# ch552t.net
KiCad netlist of a schematic drawn in Altium Designer
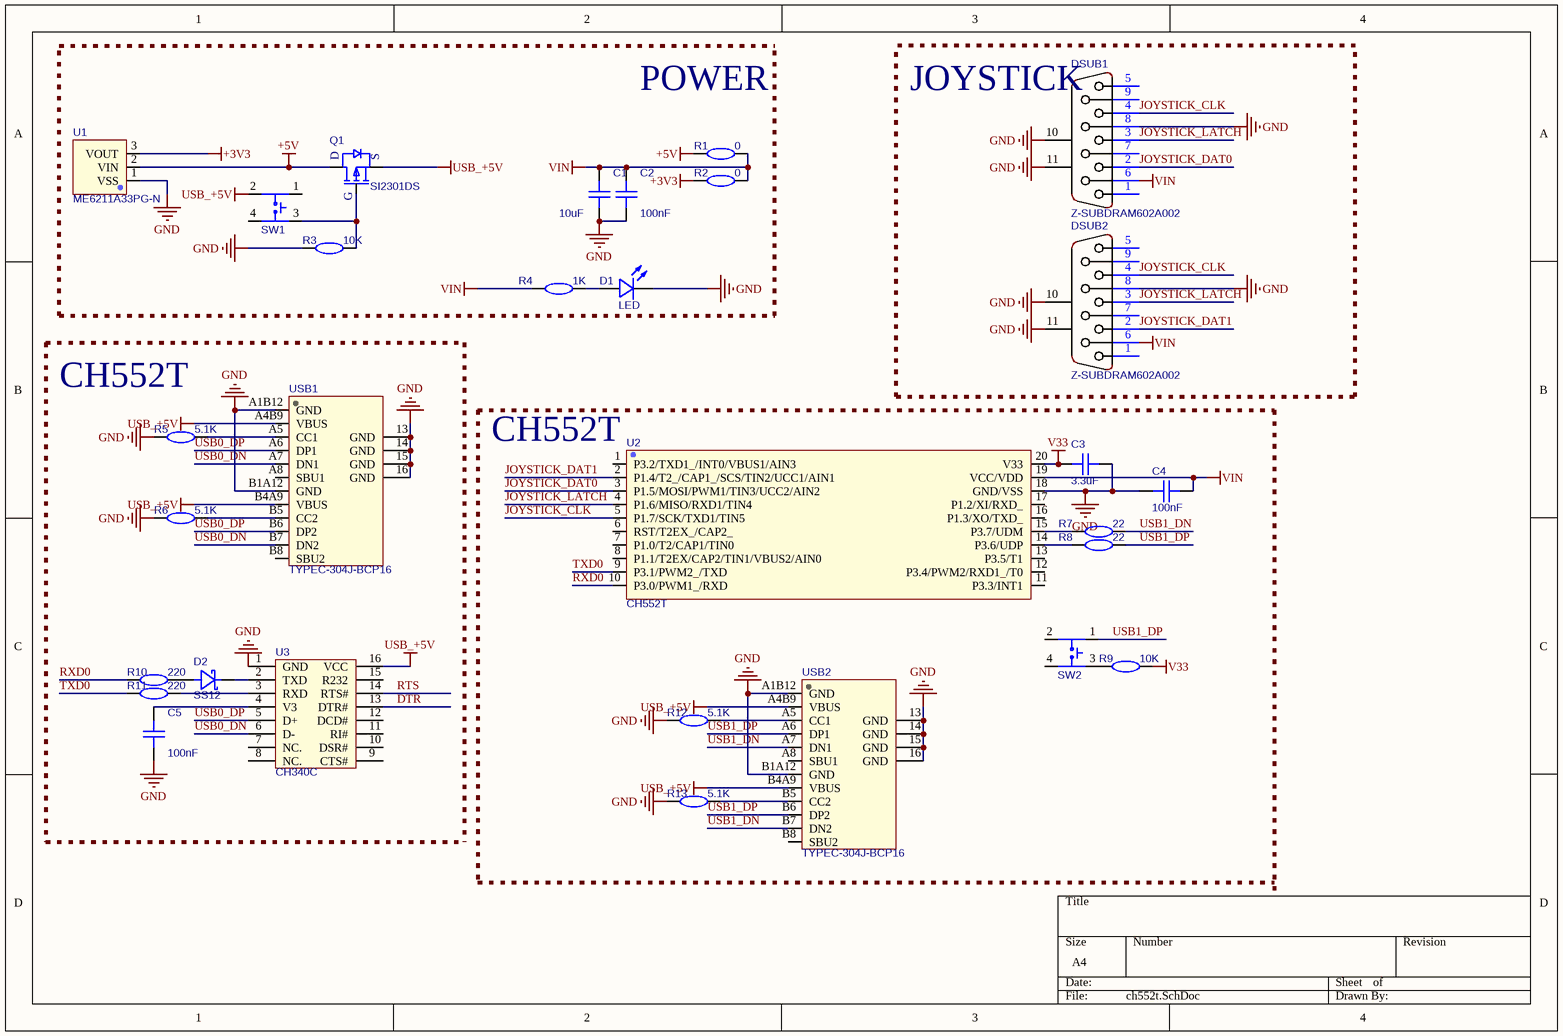
[diagram p0: ch552t.SchDoc]

(export (version "E")
  (design (tool "Eeschema 10.0.6"))
  (components
    (comp (ref "C1")
      (value "10uF")
      (footprint "C0603")
      (fields
        (field (name "BOM_SUPPLIER PART") "C325469")
        (field (name "BOM_MANUFACTURER PART") "CC0603GRNPO9BN200")
        (field (name "CONTRIBUTOR") "LCSC")
      )
      (libsource (lib "miscpcb") (part "CAP_0603"))
    )
    (comp (ref "C2")
      (value "100nF")
      (footprint "C0603")
      (fields
        (field (name "BOM_SUPPLIER PART") "C325469")
        (field (name "BOM_MANUFACTURER PART") "CC0603GRNPO9BN200")
        (field (name "CONTRIBUTOR") "LCSC")
      )
      (libsource (lib "miscpcb") (part "CAP_0603"))
    )
    (comp (ref "C3")
      (value "3.3uF")
      (footprint "C0603")
      (fields
        (field (name "BOM_SUPPLIER PART") "C325469")
        (field (name "BOM_MANUFACTURER PART") "CC0603GRNPO9BN200")
        (field (name "CONTRIBUTOR") "LCSC")
      )
      (libsource (lib "miscpcb") (part "CAP_0603"))
    )
    (comp (ref "C4")
      (value "100nF")
      (footprint "C0603")
      (fields
        (field (name "BOM_SUPPLIER PART") "C325469")
        (field (name "BOM_MANUFACTURER PART") "CC0603GRNPO9BN200")
        (field (name "CONTRIBUTOR") "LCSC")
      )
      (libsource (lib "miscpcb") (part "CAP_0603"))
    )
    (comp (ref "C5")
      (value "100nF")
      (footprint "C0603")
      (fields
        (field (name "BOM_SUPPLIER PART") "C325469")
        (field (name "BOM_MANUFACTURER PART") "CC0603GRNPO9BN200")
        (field (name "CONTRIBUTOR") "LCSC")
      )
      (libsource (lib "miscpcb") (part "CAP_0603"))
    )
    (comp (ref "D1")
      (value "LED")
      (footprint "LED-0603")
      (fields (field (name "BOM_MANUFACTURER PART") "?"))
      (libsource (lib "miscpcb") (part "LED-Y"))
    )
    (comp (ref "D2")
      (value "SS12")
      (footprint "SMA_L4.3-W2.5-LS5.0-RD")
      (description "C727049")
      (fields (field (name "CONTRIBUTOR") "LCSC"))
      (libsource (lib "esp32") (part "SS12"))
    )
    (comp (ref "DSUB1")
      (value "Z-SUBDRAM602A002")
      (footprint "DSUB-TH_Z-SUBDRAM602A002")
      (fields (field (name "BOM_SUPPLIER PART") "C115169") (field (name "CONTRIBUTOR") "LCSC"))
      (libsource (lib "esp32") (part "Z-SUBDRAM602A002"))
    )
    (comp (ref "DSUB2")
      (value "Z-SUBDRAM602A002")
      (footprint "DSUB-TH_Z-SUBDRAM602A002")
      (fields (field (name "BOM_SUPPLIER PART") "C115169") (field (name "CONTRIBUTOR") "LCSC"))
      (libsource (lib "esp32") (part "Z-SUBDRAM602A002"))
    )
    (comp (ref "Q1")
      (value "SI2301DS")
      (footprint "SOT-23-3_L2.9-W1.3-P1.90-LS2.4-BR")
      (fields (field (name "BOM_SUPPLIER PART") "C2841444") (field (name "CONTRIBUTOR") "LCSC"))
      (libsource (lib "esp32") (part "SI2301DS"))
    )
    (comp (ref "R1")
      (value "0")
      (footprint "R0603")
      (fields
        (field (name "BOM_MANUFACTURER PART") "CR0603JA0301G")
        (field (name "BOM_SUPPLIER PART") "C101323")
      )
      (libsource (lib "miscpcb") (part "RES_0603"))
    )
    (comp (ref "R2")
      (value "0")
      (footprint "R0603")
      (fields
        (field (name "BOM_MANUFACTURER PART") "CR0603JA0301G")
        (field (name "BOM_SUPPLIER PART") "C101323")
      )
      (libsource (lib "miscpcb") (part "RES_0603"))
    )
    (comp (ref "R3")
      (value "10K")
      (footprint "R0603")
      (fields
        (field (name "BOM_MANUFACTURER PART") "CR0603JA0301G")
        (field (name "BOM_SUPPLIER PART") "C101323")
      )
      (libsource (lib "miscpcb") (part "RES_0603"))
    )
    (comp (ref "R4")
      (value "1K")
      (footprint "R0603")
      (fields
        (field (name "BOM_MANUFACTURER PART") "CR0603JA0301G")
        (field (name "BOM_SUPPLIER PART") "C101323")
      )
      (libsource (lib "miscpcb") (part "RES_0603"))
    )
    (comp (ref "R5")
      (value "5.1K")
      (footprint "R0603")
      (fields
        (field (name "BOM_MANUFACTURER PART") "CR0603JA0301G")
        (field (name "BOM_SUPPLIER PART") "C101323")
      )
      (libsource (lib "miscpcb") (part "RES_0603"))
    )
    (comp (ref "R6")
      (value "5.1K")
      (footprint "R0603")
      (fields
        (field (name "BOM_MANUFACTURER PART") "CR0603JA0301G")
        (field (name "BOM_SUPPLIER PART") "C101323")
      )
      (libsource (lib "miscpcb") (part "RES_0603"))
    )
    (comp (ref "R7")
      (value "22")
      (footprint "R0603")
      (fields
        (field (name "BOM_MANUFACTURER PART") "CR0603JA0301G")
        (field (name "BOM_SUPPLIER PART") "C101323")
      )
      (libsource (lib "miscpcb") (part "RES_0603"))
    )
    (comp (ref "R8")
      (value "22")
      (footprint "R0603")
      (fields
        (field (name "BOM_MANUFACTURER PART") "CR0603JA0301G")
        (field (name "BOM_SUPPLIER PART") "C101323")
      )
      (libsource (lib "miscpcb") (part "RES_0603"))
    )
    (comp (ref "R9")
      (value "10K")
      (footprint "R0603")
      (fields
        (field (name "BOM_MANUFACTURER PART") "CR0603JA0301G")
        (field (name "BOM_SUPPLIER PART") "C101323")
      )
      (libsource (lib "miscpcb") (part "RES_0603"))
    )
    (comp (ref "R10")
      (value "220")
      (footprint "R0603")
      (fields
        (field (name "BOM_MANUFACTURER PART") "CR0603JA0301G")
        (field (name "BOM_SUPPLIER PART") "C101323")
      )
      (libsource (lib "miscpcb") (part "RES_0603"))
    )
    (comp (ref "R11")
      (value "220")
      (footprint "R0603")
      (fields
        (field (name "BOM_MANUFACTURER PART") "CR0603JA0301G")
        (field (name "BOM_SUPPLIER PART") "C101323")
      )
      (libsource (lib "miscpcb") (part "RES_0603"))
    )
    (comp (ref "R12")
      (value "5.1K")
      (footprint "R0603")
      (fields
        (field (name "BOM_MANUFACTURER PART") "CR0603JA0301G")
        (field (name "BOM_SUPPLIER PART") "C101323")
      )
      (libsource (lib "miscpcb") (part "RES_0603"))
    )
    (comp (ref "R13")
      (value "5.1K")
      (footprint "R0603")
      (fields
        (field (name "BOM_MANUFACTURER PART") "CR0603JA0301G")
        (field (name "BOM_SUPPLIER PART") "C101323")
      )
      (libsource (lib "miscpcb") (part "RES_0603"))
    )
    (comp (ref "SW1")
      (value "TS-1071SA-A3B3-D4")
      (footprint "KEY-SMD_4P-L3.5-W3.0-P1.40-LS4.6")
      (fields (field (name "BOM_SUPPLIER PART") "C498309") (field (name "CONTRIBUTOR") "LCSC"))
      (libsource (lib "esp32") (part "TS-1071SA-A3B3-D4"))
    )
    (comp (ref "SW2")
      (value "TS-1071SA-A3B3-D4")
      (footprint "KEY-SMD_4P-L3.5-W3.0-P1.40-LS4.6")
      (fields (field (name "BOM_SUPPLIER PART") "C498309") (field (name "CONTRIBUTOR") "LCSC"))
      (libsource (lib "esp32") (part "TS-1071SA-A3B3-D4"))
    )
    (comp (ref "U1")
      (value "ME6211A33PG-N")
      (footprint "SOT-89_L4.5-W2.5-P1.50-LS4.2-BR")
      (fields (field (name "BOM_SUPPLIER PART") "C236673") (field (name "CONTRIBUTOR") "LCSC"))
      (libsource (lib "esp32") (part "ME6211A33PG-N"))
    )
    (comp (ref "U2")
      (value "CH552T")
      (footprint "TSSOP-20_L6.5-W4.4-P0.65-LS6.4-BL")
      (fields (field (name "BOM_SUPPLIER PART") "C111367"))
      (libsource (lib "esp32") (part "CH552T"))
    )
    (comp (ref "U3")
      (value "CH340C")
      (footprint "SOP-16_L10.0-W3.9-P1.27-LS6.0-BL")
      (fields (field (name "BOM_SUPPLIER PART") "C84681"))
      (libsource (lib "esp32") (part "CH340C"))
    )
    (comp (ref "USB1")
      (value "TYPEC-304J-BCP16")
      (footprint "USB-C-SMD_TYPEC-304J-BCP16")
      (fields (field (name "BOM_SUPPLIER PART") "C2835315") (field (name "CONTRIBUTOR") "LCSC"))
      (libsource (lib "esp32") (part "TYPEC-304J-BCP16"))
    )
    (comp (ref "USB2")
      (value "TYPEC-304J-BCP16")
      (footprint "USB-C-SMD_TYPEC-304J-BCP16")
      (fields (field (name "BOM_SUPPLIER PART") "C2835315") (field (name "CONTRIBUTOR") "LCSC"))
      (libsource (lib "esp32") (part "TYPEC-304J-BCP16"))
    )
  )
  (nets
    (net (code "1") (name "+3V3") (class "Default")
      (node (ref "R2") (pin "2") (pinfunction "2_2") (pintype "passive"))
      (node (ref "U1") (pin "3") (pinfunction "VOUT_3") (pintype "passive"))
    )
    (net (code "2") (name "+5V") (class "Default")
      (node (ref "Q1") (pin "3") (pinfunction "D_3") (pintype "passive"))
      (node (ref "R1") (pin "2") (pinfunction "2_2") (pintype "passive"))
      (node (ref "U1") (pin "2") (pinfunction "VIN_2") (pintype "passive"))
    )
    (net (code "3") (name "/DTR") (class "Default")
      (node (ref "U3") (pin "13") (pinfunction "DTR#_13") (pintype "passive"))
    )
    (net (code "4") (name "/JOYSTICK_CLK") (class "Default")
      (node (ref "DSUB1") (pin "4") (pinfunction "4_4") (pintype "passive"))
      (node (ref "DSUB2") (pin "4") (pinfunction "4_4") (pintype "passive"))
      (node (ref "U2") (pin "5") (pinfunction "P1.7/SCK/TXD1/TIN5_5") (pintype "passive"))
    )
    (net (code "5") (name "/JOYSTICK_DAT0") (class "Default")
      (node (ref "DSUB1") (pin "2") (pinfunction "2_2") (pintype "passive"))
      (node (ref "U2") (pin "3") (pinfunction "P1.5/MOSI/PWM1/TIN3/UCC2/AIN2_3") (pintype "passive"))
    )
    (net (code "6") (name "/JOYSTICK_DAT1") (class "Default")
      (node (ref "DSUB2") (pin "2") (pinfunction "2_2") (pintype "passive"))
      (node (ref "U2") (pin "2") (pinfunction "P1.4/T2_/CAP1_/SCS/TIN2/UCC1/AIN1_2") (pintype "passive"))
    )
    (net (code "7") (name "/JOYSTICK_LATCH") (class "Default")
      (node (ref "DSUB1") (pin "3") (pinfunction "3_3") (pintype "passive"))
      (node (ref "DSUB2") (pin "3") (pinfunction "3_3") (pintype "passive"))
      (node (ref "U2") (pin "4") (pinfunction "P1.6/MISO/RXD1/TIN4_4") (pintype "passive"))
    )
    (net (code "8") (name "/RTS") (class "Default")
      (node (ref "U3") (pin "14") (pinfunction "RTS#_14") (pintype "passive"))
    )
    (net (code "9") (name "/RXD0") (class "Default")
      (node (ref "R10") (pin "2") (pinfunction "2_2") (pintype "passive"))
      (node (ref "U2") (pin "10") (pinfunction "P3.0/PWM1_/RXD_10") (pintype "passive"))
    )
    (net (code "10") (name "/TXD0") (class "Default")
      (node (ref "R11") (pin "2") (pinfunction "2_2") (pintype "passive"))
      (node (ref "U2") (pin "9") (pinfunction "P3.1/PWM2_/TXD_9") (pintype "passive"))
    )
    (net (code "11") (name "/USB0_DN") (class "Default")
      (node (ref "U3") (pin "6") (pinfunction "D-_6") (pintype "passive"))
      (node (ref "USB1") (pin "A7") (pinfunction "DN1_A7") (pintype "passive"))
      (node (ref "USB1") (pin "B7") (pinfunction "DN2_B7") (pintype "passive"))
    )
    (net (code "12") (name "/USB0_DP") (class "Default")
      (node (ref "U3") (pin "5") (pinfunction "D+_5") (pintype "passive"))
      (node (ref "USB1") (pin "A6") (pinfunction "DP1_A6") (pintype "passive"))
      (node (ref "USB1") (pin "B6") (pinfunction "DP2_B6") (pintype "passive"))
    )
    (net (code "13") (name "/USB1_DN") (class "Default")
      (node (ref "R7") (pin "1") (pinfunction "1_1") (pintype "passive"))
      (node (ref "USB2") (pin "A7") (pinfunction "DN1_A7") (pintype "passive"))
      (node (ref "USB2") (pin "B7") (pinfunction "DN2_B7") (pintype "passive"))
    )
    (net (code "14") (name "/USB1_DP") (class "Default")
      (node (ref "R8") (pin "1") (pinfunction "1_1") (pintype "passive"))
      (node (ref "SW2") (pin "1") (pinfunction "1_1") (pintype "passive"))
      (node (ref "USB2") (pin "A6") (pinfunction "DP1_A6") (pintype "passive"))
      (node (ref "USB2") (pin "B6") (pinfunction "DP2_B6") (pintype "passive"))
    )
    (net (code "15") (name "GND") (class "Default")
      (node (ref "C1") (pin "1") (pinfunction "1_1") (pintype "passive"))
      (node (ref "C2") (pin "1") (pinfunction "1_1") (pintype "passive"))
      (node (ref "C3") (pin "1") (pinfunction "1_1") (pintype "passive"))
      (node (ref "C4") (pin "2") (pinfunction "2_2") (pintype "passive"))
      (node (ref "C5") (pin "1") (pinfunction "1_1") (pintype "passive"))
      (node (ref "D1") (pin "2") (pinfunction "K_2") (pintype "passive"))
      (node (ref "DSUB1") (pin "10") (pinfunction "MH1_10") (pintype "passive"))
      (node (ref "DSUB1") (pin "11") (pinfunction "MH2_11") (pintype "passive"))
      (node (ref "DSUB1") (pin "8") (pinfunction "8_8") (pintype "passive"))
      (node (ref "DSUB2") (pin "10") (pinfunction "MH1_10") (pintype "passive"))
      (node (ref "DSUB2") (pin "11") (pinfunction "MH2_11") (pintype "passive"))
      (node (ref "DSUB2") (pin "8") (pinfunction "8_8") (pintype "passive"))
      (node (ref "R12") (pin "2") (pinfunction "2_2") (pintype "passive"))
      (node (ref "R13") (pin "2") (pinfunction "2_2") (pintype "passive"))
      (node (ref "R3") (pin "2") (pinfunction "2_2") (pintype "passive"))
      (node (ref "R5") (pin "2") (pinfunction "2_2") (pintype "passive"))
      (node (ref "R6") (pin "2") (pinfunction "2_2") (pintype "passive"))
      (node (ref "U1") (pin "1") (pinfunction "VSS_1") (pintype "passive"))
      (node (ref "U2") (pin "18") (pinfunction "GND/VSS_18") (pintype "passive"))
      (node (ref "U3") (pin "1") (pinfunction "GND_1") (pintype "passive"))
      (node (ref "USB1") (pin "13") (pinfunction "GND_13") (pintype "passive"))
      (node (ref "USB1") (pin "14") (pinfunction "GND_14") (pintype "passive"))
      (node (ref "USB1") (pin "15") (pinfunction "GND_15") (pintype "passive"))
      (node (ref "USB1") (pin "16") (pinfunction "GND_16") (pintype "passive"))
      (node (ref "USB1") (pin "A1B12") (pinfunction "GND_A1B12") (pintype "passive"))
      (node (ref "USB1") (pin "B1A12") (pinfunction "GND_B1A12") (pintype "passive"))
      (node (ref "USB2") (pin "13") (pinfunction "GND_13") (pintype "passive"))
      (node (ref "USB2") (pin "14") (pinfunction "GND_14") (pintype "passive"))
      (node (ref "USB2") (pin "15") (pinfunction "GND_15") (pintype "passive"))
      (node (ref "USB2") (pin "16") (pinfunction "GND_16") (pintype "passive"))
      (node (ref "USB2") (pin "A1B12") (pinfunction "GND_A1B12") (pintype "passive"))
      (node (ref "USB2") (pin "B1A12") (pinfunction "GND_B1A12") (pintype "passive"))
    )
    (net (code "16") (name "Net-(D1-A)") (class "Default")
      (node (ref "D1") (pin "1") (pinfunction "A_1") (pintype "passive"))
      (node (ref "R4") (pin "1") (pinfunction "1_1") (pintype "passive"))
    )
    (net (code "17") (name "Net-(D2-Pad2)") (class "Default")
      (node (ref "D2") (pin "2") (pinfunction "2_2") (pintype "passive"))
      (node (ref "R10") (pin "1") (pinfunction "1_1") (pintype "passive"))
    )
    (net (code "18") (name "Net-(Q1-G)") (class "Default")
      (node (ref "Q1") (pin "1") (pinfunction "G_1") (pintype "passive"))
      (node (ref "R3") (pin "1") (pinfunction "1_1") (pintype "passive"))
      (node (ref "SW1") (pin "3") (pinfunction "3_3") (pintype "passive"))
    )
    (net (code "19") (name "Net-(R9-Pad2)") (class "Default")
      (node (ref "R9") (pin "2") (pinfunction "2_2") (pintype "passive"))
      (node (ref "SW2") (pin "3") (pinfunction "3_3") (pintype "passive"))
    )
    (net (code "20") (name "Net-(U2-P3.6{slash}UDP)") (class "Default")
      (node (ref "R8") (pin "2") (pinfunction "2_2") (pintype "passive"))
      (node (ref "U2") (pin "14") (pinfunction "P3.6/UDP_14") (pintype "passive"))
    )
    (net (code "21") (name "Net-(U2-P3.7{slash}UDM)") (class "Default")
      (node (ref "R7") (pin "2") (pinfunction "2_2") (pintype "passive"))
      (node (ref "U2") (pin "15") (pinfunction "P3.7/UDM_15") (pintype "passive"))
    )
    (net (code "22") (name "Net-(U3-RXD)") (class "Default")
      (node (ref "R11") (pin "1") (pinfunction "1_1") (pintype "passive"))
      (node (ref "U3") (pin "3") (pinfunction "RXD_3") (pintype "passive"))
    )
    (net (code "23") (name "Net-(U3-TXD)") (class "Default")
      (node (ref "D2") (pin "1") (pinfunction "1_1") (pintype "passive"))
      (node (ref "U3") (pin "2") (pinfunction "TXD_2") (pintype "passive"))
    )
    (net (code "24") (name "Net-(U3-V3)") (class "Default")
      (node (ref "C5") (pin "2") (pinfunction "2_2") (pintype "passive"))
      (node (ref "U3") (pin "4") (pinfunction "V3_4") (pintype "passive"))
    )
    (net (code "25") (name "Net-(USB1-CC1)") (class "Default")
      (node (ref "R5") (pin "1") (pinfunction "1_1") (pintype "passive"))
      (node (ref "USB1") (pin "A5") (pinfunction "CC1_A5") (pintype "passive"))
    )
    (net (code "26") (name "Net-(USB1-CC2)") (class "Default")
      (node (ref "R6") (pin "1") (pinfunction "1_1") (pintype "passive"))
      (node (ref "USB1") (pin "B5") (pinfunction "CC2_B5") (pintype "passive"))
    )
    (net (code "27") (name "Net-(USB2-CC1)") (class "Default")
      (node (ref "R12") (pin "1") (pinfunction "1_1") (pintype "passive"))
      (node (ref "USB2") (pin "A5") (pinfunction "CC1_A5") (pintype "passive"))
    )
    (net (code "28") (name "Net-(USB2-CC2)") (class "Default")
      (node (ref "R13") (pin "1") (pinfunction "1_1") (pintype "passive"))
      (node (ref "USB2") (pin "B5") (pinfunction "CC2_B5") (pintype "passive"))
    )
    (net (code "29") (name "USB_+5V") (class "Default")
      (node (ref "Q1") (pin "2") (pinfunction "S_2") (pintype "passive"))
      (node (ref "SW1") (pin "2") (pinfunction "2_2") (pintype "passive"))
      (node (ref "U3") (pin "16") (pinfunction "VCC_16") (pintype "passive"))
      (node (ref "USB1") (pin "A4B9") (pinfunction "VBUS_A4B9") (pintype "passive"))
      (node (ref "USB1") (pin "B4A9") (pinfunction "VBUS_B4A9") (pintype "passive"))
      (node (ref "USB2") (pin "A4B9") (pinfunction "VBUS_A4B9") (pintype "passive"))
      (node (ref "USB2") (pin "B4A9") (pinfunction "VBUS_B4A9") (pintype "passive"))
    )
    (net (code "30") (name "V33") (class "Default")
      (node (ref "C3") (pin "2") (pinfunction "2_2") (pintype "passive"))
      (node (ref "R9") (pin "1") (pinfunction "1_1") (pintype "passive"))
      (node (ref "U2") (pin "20") (pinfunction "V33_20") (pintype "passive"))
    )
    (net (code "31") (name "VIN") (class "Default")
      (node (ref "C1") (pin "2") (pinfunction "2_2") (pintype "passive"))
      (node (ref "C2") (pin "2") (pinfunction "2_2") (pintype "passive"))
      (node (ref "C4") (pin "1") (pinfunction "1_1") (pintype "passive"))
      (node (ref "DSUB1") (pin "6") (pinfunction "6_6") (pintype "passive"))
      (node (ref "DSUB2") (pin "6") (pinfunction "6_6") (pintype "passive"))
      (node (ref "R1") (pin "1") (pinfunction "1_1") (pintype "passive"))
      (node (ref "R2") (pin "1") (pinfunction "1_1") (pintype "passive"))
      (node (ref "R4") (pin "2") (pinfunction "2_2") (pintype "passive"))
      (node (ref "U2") (pin "19") (pinfunction "VCC/VDD_19") (pintype "passive"))
    )
    (net (code "32") (name "unconnected-(DSUB1-Pad1)") (class "Default")
      (node (ref "DSUB1") (pin "1") (pinfunction "1_1") (pintype "passive"))
    )
    (net (code "33") (name "unconnected-(DSUB1-Pad5)") (class "Default")
      (node (ref "DSUB1") (pin "5") (pinfunction "5_5") (pintype "passive"))
    )
    (net (code "34") (name "unconnected-(DSUB1-Pad7)") (class "Default")
      (node (ref "DSUB1") (pin "7") (pinfunction "7_7") (pintype "passive"))
    )
    (net (code "35") (name "unconnected-(DSUB1-Pad9)") (class "Default")
      (node (ref "DSUB1") (pin "9") (pinfunction "9_9") (pintype "passive"))
    )
    (net (code "36") (name "unconnected-(DSUB2-Pad1)") (class "Default")
      (node (ref "DSUB2") (pin "1") (pinfunction "1_1") (pintype "passive"))
    )
    (net (code "37") (name "unconnected-(DSUB2-Pad5)") (class "Default")
      (node (ref "DSUB2") (pin "5") (pinfunction "5_5") (pintype "passive"))
    )
    (net (code "38") (name "unconnected-(DSUB2-Pad7)") (class "Default")
      (node (ref "DSUB2") (pin "7") (pinfunction "7_7") (pintype "passive"))
    )
    (net (code "39") (name "unconnected-(DSUB2-Pad9)") (class "Default")
      (node (ref "DSUB2") (pin "9") (pinfunction "9_9") (pintype "passive"))
    )
    (net (code "40") (name "unconnected-(SW1-Pad1)") (class "Default")
      (node (ref "SW1") (pin "1") (pinfunction "1_1") (pintype "passive"))
    )
    (net (code "41") (name "unconnected-(SW1-Pad4)") (class "Default")
      (node (ref "SW1") (pin "4") (pinfunction "4_4") (pintype "passive"))
    )
    (net (code "42") (name "unconnected-(SW2-Pad2)") (class "Default")
      (node (ref "SW2") (pin "2") (pinfunction "2_2") (pintype "passive"))
    )
    (net (code "43") (name "unconnected-(SW2-Pad4)") (class "Default")
      (node (ref "SW2") (pin "4") (pinfunction "4_4") (pintype "passive"))
    )
    (net (code "44") (name "unconnected-(U2-P1.0{slash}T2{slash}CAP1{slash}TIN0-Pad7)") (class "Default")
      (node (ref "U2") (pin "7") (pinfunction "P1.0/T2/CAP1/TIN0_7") (pintype "passive"))
    )
    (net (code "45") (name "unconnected-(U2-P1.1{slash}T2EX{slash}CAP2{slash}TIN1{slash}VBUS2{slash}AIN0-Pad8)") (class "Default")
      (node (ref "U2") (pin "8") (pinfunction "P1.1/T2EX/CAP2/TIN1/VBUS2/AIN0_8") (pintype "passive"))
    )
    (net (code "46") (name "unconnected-(U2-P1.2{slash}XI{slash}RXD_-Pad17)") (class "Default")
      (node (ref "U2") (pin "17") (pinfunction "P1.2/XI/RXD__17") (pintype "passive"))
    )
    (net (code "47") (name "unconnected-(U2-P1.3{slash}XO{slash}TXD_-Pad16)") (class "Default")
      (node (ref "U2") (pin "16") (pinfunction "P1.3/XO/TXD__16") (pintype "passive"))
    )
    (net (code "48") (name "unconnected-(U2-P3.2{slash}TXD1_{slash}INT0{slash}VBUS1{slash}AIN3-Pad1)") (class "Default")
      (node (ref "U2") (pin "1") (pinfunction "P3.2/TXD1_/INT0/VBUS1/AIN3_1") (pintype "passive"))
    )
    (net (code "49") (name "unconnected-(U2-P3.3{slash}INT1-Pad11)") (class "Default")
      (node (ref "U2") (pin "11") (pinfunction "P3.3/INT1_11") (pintype "passive"))
    )
    (net (code "50") (name "unconnected-(U2-P3.4{slash}PWM2{slash}RXD1_{slash}T0-Pad12)") (class "Default")
      (node (ref "U2") (pin "12") (pinfunction "P3.4/PWM2/RXD1_/T0_12") (pintype "passive"))
    )
    (net (code "51") (name "unconnected-(U2-P3.5{slash}T1-Pad13)") (class "Default")
      (node (ref "U2") (pin "13") (pinfunction "P3.5/T1_13") (pintype "passive"))
    )
    (net (code "52") (name "unconnected-(U2-RST{slash}T2EX_{slash}CAP2_-Pad6)") (class "Default")
      (node (ref "U2") (pin "6") (pinfunction "RST/T2EX_/CAP2__6") (pintype "passive"))
    )
    (net (code "53") (name "unconnected-(U3-CTS#-Pad9)") (class "Default")
      (node (ref "U3") (pin "9") (pinfunction "CTS#_9") (pintype "passive"))
    )
    (net (code "54") (name "unconnected-(U3-DCD#-Pad12)") (class "Default")
      (node (ref "U3") (pin "12") (pinfunction "DCD#_12") (pintype "passive"))
    )
    (net (code "55") (name "unconnected-(U3-DSR#-Pad10)") (class "Default")
      (node (ref "U3") (pin "10") (pinfunction "DSR#_10") (pintype "passive"))
    )
    (net (code "56") (name "unconnected-(U3-NC.-Pad7)") (class "Default")
      (node (ref "U3") (pin "7") (pinfunction "NC._7") (pintype "passive"))
    )
    (net (code "57") (name "unconnected-(U3-NC.-Pad8)") (class "Default")
      (node (ref "U3") (pin "8") (pinfunction "NC._8") (pintype "passive"))
    )
    (net (code "58") (name "unconnected-(U3-R232-Pad15)") (class "Default")
      (node (ref "U3") (pin "15") (pinfunction "R232_15") (pintype "passive"))
    )
    (net (code "59") (name "unconnected-(U3-RI#-Pad11)") (class "Default")
      (node (ref "U3") (pin "11") (pinfunction "RI#_11") (pintype "passive"))
    )
    (net (code "60") (name "unconnected-(USB1-SBU1-PadA8)") (class "Default")
      (node (ref "USB1") (pin "A8") (pinfunction "SBU1_A8") (pintype "passive"))
    )
    (net (code "61") (name "unconnected-(USB1-SBU2-PadB8)") (class "Default")
      (node (ref "USB1") (pin "B8") (pinfunction "SBU2_B8") (pintype "passive"))
    )
    (net (code "62") (name "unconnected-(USB2-SBU1-PadA8)") (class "Default")
      (node (ref "USB2") (pin "A8") (pinfunction "SBU1_A8") (pintype "passive"))
    )
    (net (code "63") (name "unconnected-(USB2-SBU2-PadB8)") (class "Default")
      (node (ref "USB2") (pin "B8") (pinfunction "SBU2_B8") (pintype "passive"))
    )
  )
)
